# sensor_board_Final.net
KiCad netlist of a schematic drawn in EAGLE
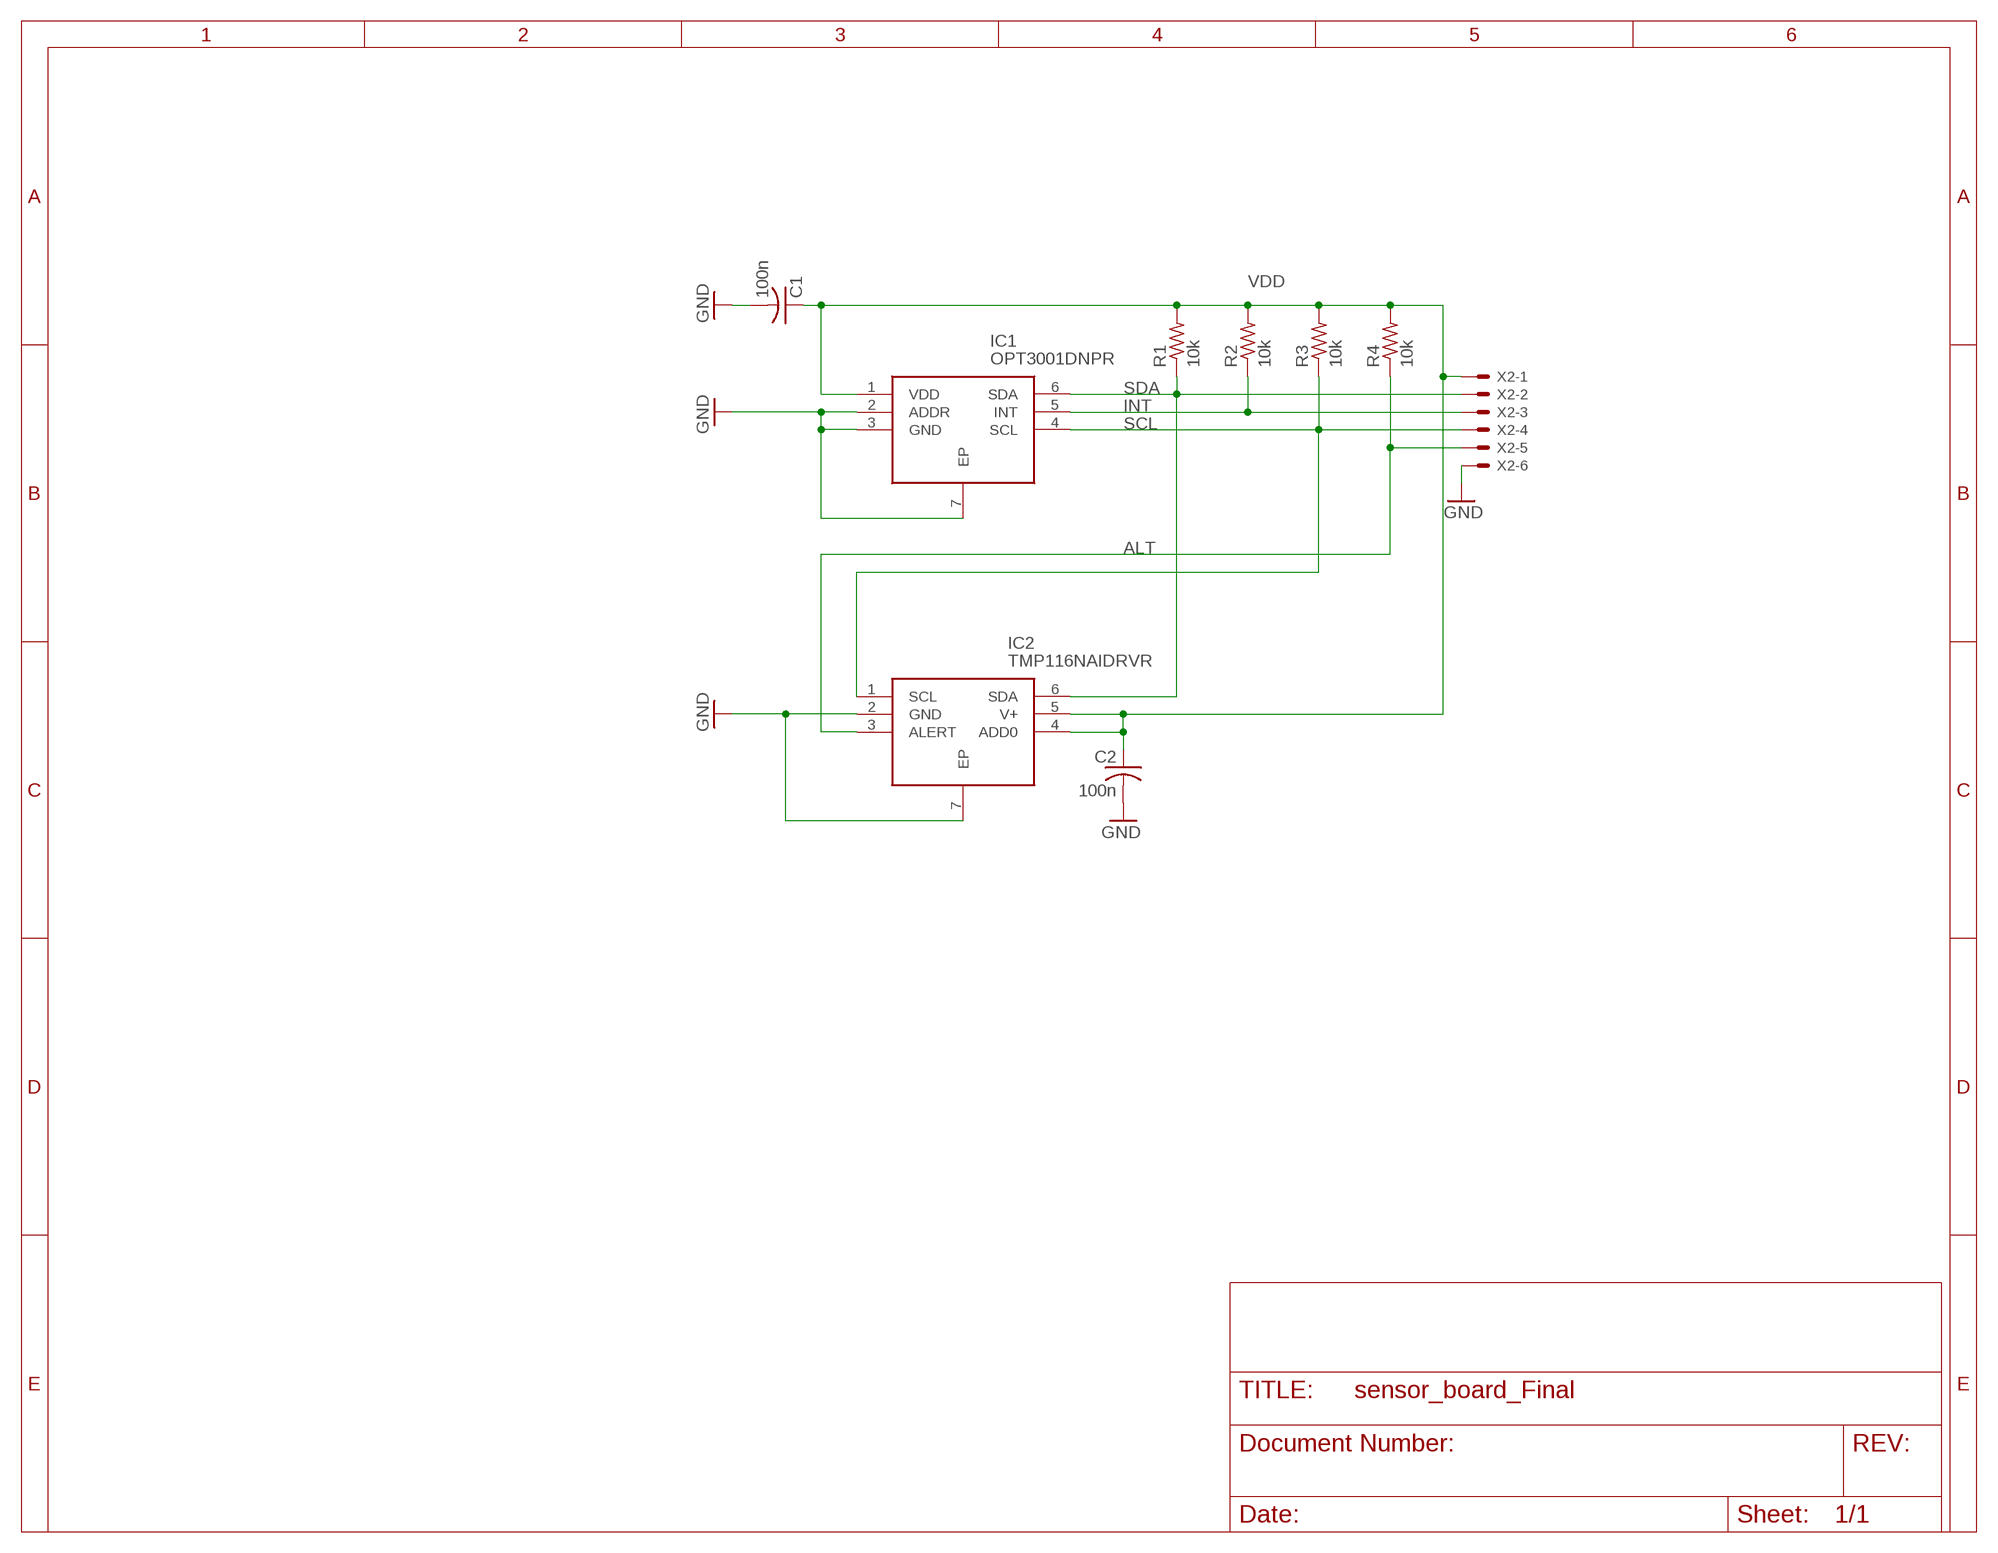
[diagram p0: schematic, sheet 1]

(export (version "E")
  (design (tool "Eeschema 10.0.6"))
  (components
    (comp (ref "C1")
      (value "100n")
      (footprint "eagle-import:C0805")
      (libsource (lib "eagle-import") (part "C-USC0805"))
    )
    (comp (ref "C2")
      (value "100n")
      (footprint "eagle-import:C0805")
      (libsource (lib "eagle-import") (part "C-USC0805"))
    )
    (comp (ref "IC1")
      (value "OPT3001DNPR")
      (footprint "eagle-import:SON65P200X200X65-7N")
      (fields (field (name "MOUSER_PART_NUMBER") "595-OPT3001DNPR"))
      (libsource (lib "eagle-import") (part "OPT3001DNPR"))
    )
    (comp (ref "IC2")
      (value "TMP116NAIDRVR")
      (footprint "eagle-import:SON65P200X200X80-7N")
      (fields (field (name "MOUSER_PART_NUMBER") "595-TMP116NAIDRVR"))
      (libsource (lib "eagle-import") (part "TMP116NAIDRVR"))
    )
    (comp (ref "R1")
      (value "10k")
      (footprint "eagle-import:R0603")
      (libsource (lib "eagle-import") (part "R-US_R0603"))
    )
    (comp (ref "R2")
      (value "10k")
      (footprint "eagle-import:R0603")
      (libsource (lib "eagle-import") (part "R-US_R0603"))
    )
    (comp (ref "R3")
      (value "10k")
      (footprint "eagle-import:R0603")
      (libsource (lib "eagle-import") (part "R-US_R0603"))
    )
    (comp (ref "R4")
      (value "10k")
      (footprint "eagle-import:R0603")
      (libsource (lib "eagle-import") (part "R-US_R0603"))
    )
    (comp (ref "X2")
      (value "22-23-2061")
      (footprint "eagle-import:22-23-2061")
      (fields (field (name "MF") "MOLEX"))
      (libsource (lib "eagle-import") (part "22-23-2061"))
    )
  )
  (nets
    (net (code "1") (name "/ALT") (class "Default")
      (node (ref "IC2") (pin "3") (pinfunction "ALERT_3") (pintype "bidirectional"))
      (node (ref "R4") (pin "1") (pinfunction "1_1") (pintype "passive"))
      (node (ref "X2") (pin "5") (pinfunction "S_5") (pintype "passive"))
    )
    (net (code "2") (name "/INT") (class "Default")
      (node (ref "IC1") (pin "5") (pinfunction "INT_5") (pintype "bidirectional"))
      (node (ref "R2") (pin "1") (pinfunction "1_1") (pintype "passive"))
      (node (ref "X2") (pin "3") (pinfunction "S_3") (pintype "passive"))
    )
    (net (code "3") (name "/SCL") (class "Default")
      (node (ref "IC1") (pin "4") (pinfunction "SCL_4") (pintype "bidirectional"))
      (node (ref "IC2") (pin "1") (pinfunction "SCL_1") (pintype "bidirectional"))
      (node (ref "R3") (pin "1") (pinfunction "1_1") (pintype "passive"))
      (node (ref "X2") (pin "4") (pinfunction "S_4") (pintype "passive"))
    )
    (net (code "4") (name "/SDA") (class "Default")
      (node (ref "IC1") (pin "6") (pinfunction "SDA_6") (pintype "bidirectional"))
      (node (ref "IC2") (pin "6") (pinfunction "SDA_6") (pintype "bidirectional"))
      (node (ref "R1") (pin "1") (pinfunction "1_1") (pintype "passive"))
      (node (ref "X2") (pin "2") (pinfunction "S_2") (pintype "passive"))
    )
    (net (code "5") (name "/VDD") (class "Default")
      (node (ref "C1") (pin "1") (pinfunction "1_1") (pintype "passive"))
      (node (ref "C2") (pin "1") (pinfunction "1_1") (pintype "passive"))
      (node (ref "IC1") (pin "1") (pinfunction "VDD_1") (pintype "bidirectional"))
      (node (ref "IC2") (pin "4") (pinfunction "ADD0_4") (pintype "bidirectional"))
      (node (ref "IC2") (pin "5") (pinfunction "V+_5") (pintype "bidirectional"))
      (node (ref "R1") (pin "2") (pinfunction "2_2") (pintype "passive"))
      (node (ref "R2") (pin "2") (pinfunction "2_2") (pintype "passive"))
      (node (ref "R3") (pin "2") (pinfunction "2_2") (pintype "passive"))
      (node (ref "R4") (pin "2") (pinfunction "2_2") (pintype "passive"))
      (node (ref "X2") (pin "1") (pinfunction "S_1") (pintype "passive"))
    )
    (net (code "6") (name "GND") (class "Default")
      (node (ref "C1") (pin "2") (pinfunction "2_2") (pintype "passive"))
      (node (ref "C2") (pin "2") (pinfunction "2_2") (pintype "passive"))
      (node (ref "IC1") (pin "2") (pinfunction "ADDR_2") (pintype "bidirectional"))
      (node (ref "IC1") (pin "3") (pinfunction "GND_3") (pintype "bidirectional"))
      (node (ref "IC1") (pin "7") (pinfunction "EP_7") (pintype "bidirectional"))
      (node (ref "IC2") (pin "2") (pinfunction "GND_2") (pintype "bidirectional"))
      (node (ref "IC2") (pin "7") (pinfunction "EP_7") (pintype "bidirectional"))
      (node (ref "X2") (pin "6") (pinfunction "S_6") (pintype "passive"))
    )
  )
)
